# QUTMS-TSAL-S01.net
KiCad netlist of a schematic drawn in Altium Designer
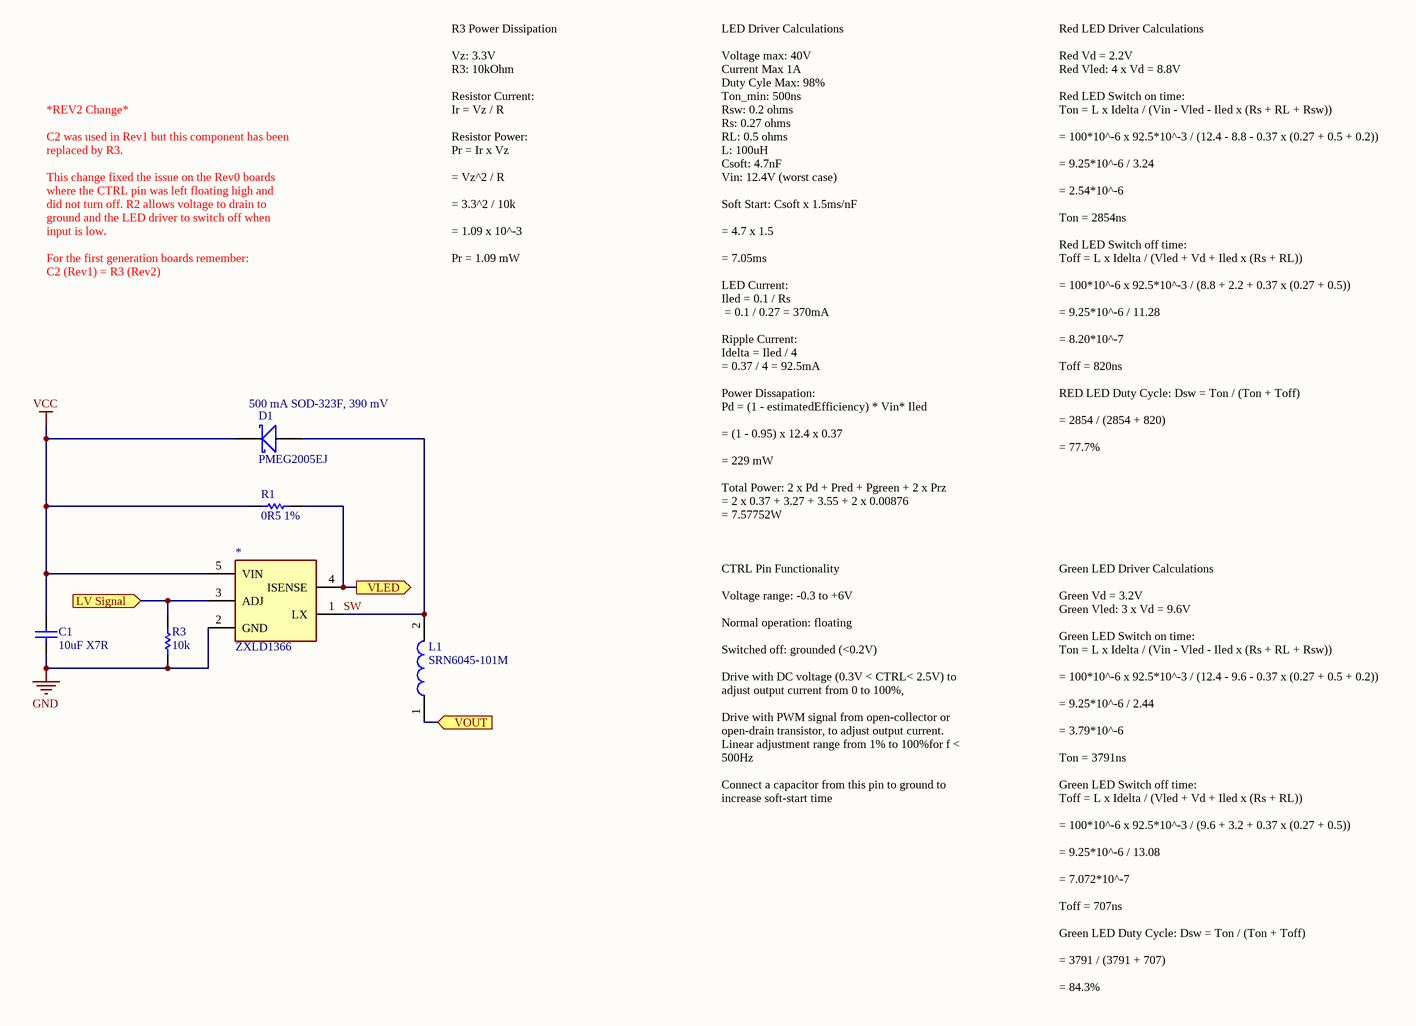
[diagram p0: QUTMS-TSAL-S01.SchDoc]

(export (version "E")
  (design (tool "Eeschema 10.0.6"))
  (components
    (comp (ref "*")
      (value "ZXLD1366")
      (footprint "SOT95P280X100-5N")
      (libsource (lib "QUTMS_PowerSupplyLibrary") (part "ZXLD136ET5TA"))
    )
    (comp (ref "C1")
      (value "10uF X7R")
      (footprint "Cap_Ceramic_0603")
      (description "Capacitor, Ceramic, SMD, 10uF, 50V, 5%, X7R, 0603")
      (libsource (lib "StandardCapacitors") (part "10uF 50V 5% X7R 0603"))
    )
    (comp (ref "D1")
      (value "PMEG2005EJ")
      (footprint "SOD-323F")
      (description "Diode, Schottky, SMD, 20 V, 500 mA, Single, SOD-323F, 2 Pins, 390 mV")
      (libsource (lib "QUTMS_DiodeLibrary") (part "PMEG2005EJ"))
    )
    (comp (ref "L1")
      (value "SRN6045-101M")
      (footprint "Bourns Inductor 6x6x4.5mm")
      (description "Inductor, 100 µH, 700 mA, Semishielded, 800 mA, SRN6045 Series, 6mm x 6mm x 4.5mm")
      (libsource (lib "QUTMS_InductorLibrary") (part "SRN6045-101M"))
    )
    (comp (ref "R1")
      (value "0R5 1%")
      (footprint "RESC1005X04N")
      (description "Resistor, SMD, 0R27, 0.1W, 1%, 0603")
      (libsource (lib "StandardResistors") (part "0R27 1% 0603"))
    )
    (comp (ref "R3")
      (value "10k")
      (footprint "Res_ThinFilm_0603")
      (description "Resistor, SMD, 10k, 0.1W, 5%, 0603")
      (libsource (lib "StandardResistors") (part "10k 5% 0603"))
    )
  )
  (nets
    (net (code "1") (name "/LV Signal") (class "Default")
      (node (ref "*") (pin "3") (pinfunction "ADJ_3") (pintype "power_in"))
      (node (ref "R3") (pin "2") (pinfunction "2_2") (pintype "passive"))
    )
    (net (code "2") (name "/SW") (class "Default")
      (node (ref "*") (pin "1") (pinfunction "LX_1") (pintype "power_in"))
      (node (ref "D1") (pin "A") (pinfunction "Anode_A") (pintype "passive"))
      (node (ref "L1") (pin "2") (pinfunction "2_2") (pintype "passive"))
    )
    (net (code "3") (name "/VLED") (class "Default")
      (node (ref "*") (pin "4") (pinfunction "ISENSE_4") (pintype "power_in"))
      (node (ref "R1") (pin "2") (pinfunction "2_2") (pintype "passive"))
    )
    (net (code "4") (name "/VOUT") (class "Default")
      (node (ref "L1") (pin "1") (pinfunction "1_1") (pintype "passive"))
    )
    (net (code "5") (name "GND") (class "Default")
      (node (ref "*") (pin "2") (pinfunction "GND_2") (pintype "power_in"))
      (node (ref "C1") (pin "1") (pinfunction "1_1") (pintype "passive"))
      (node (ref "R3") (pin "1") (pinfunction "1_1") (pintype "passive"))
    )
    (net (code "6") (name "VCC") (class "Default")
      (node (ref "*") (pin "5") (pinfunction "VIN_5") (pintype "power_in"))
      (node (ref "C1") (pin "2") (pinfunction "2_2") (pintype "passive"))
      (node (ref "D1") (pin "K") (pinfunction "Cathode_K") (pintype "passive"))
      (node (ref "R1") (pin "1") (pinfunction "1_1") (pintype "passive"))
    )
  )
)
